# USB_Downstream_Type_C_Port_3.net
KiCad netlist of a schematic drawn in Altium Designer
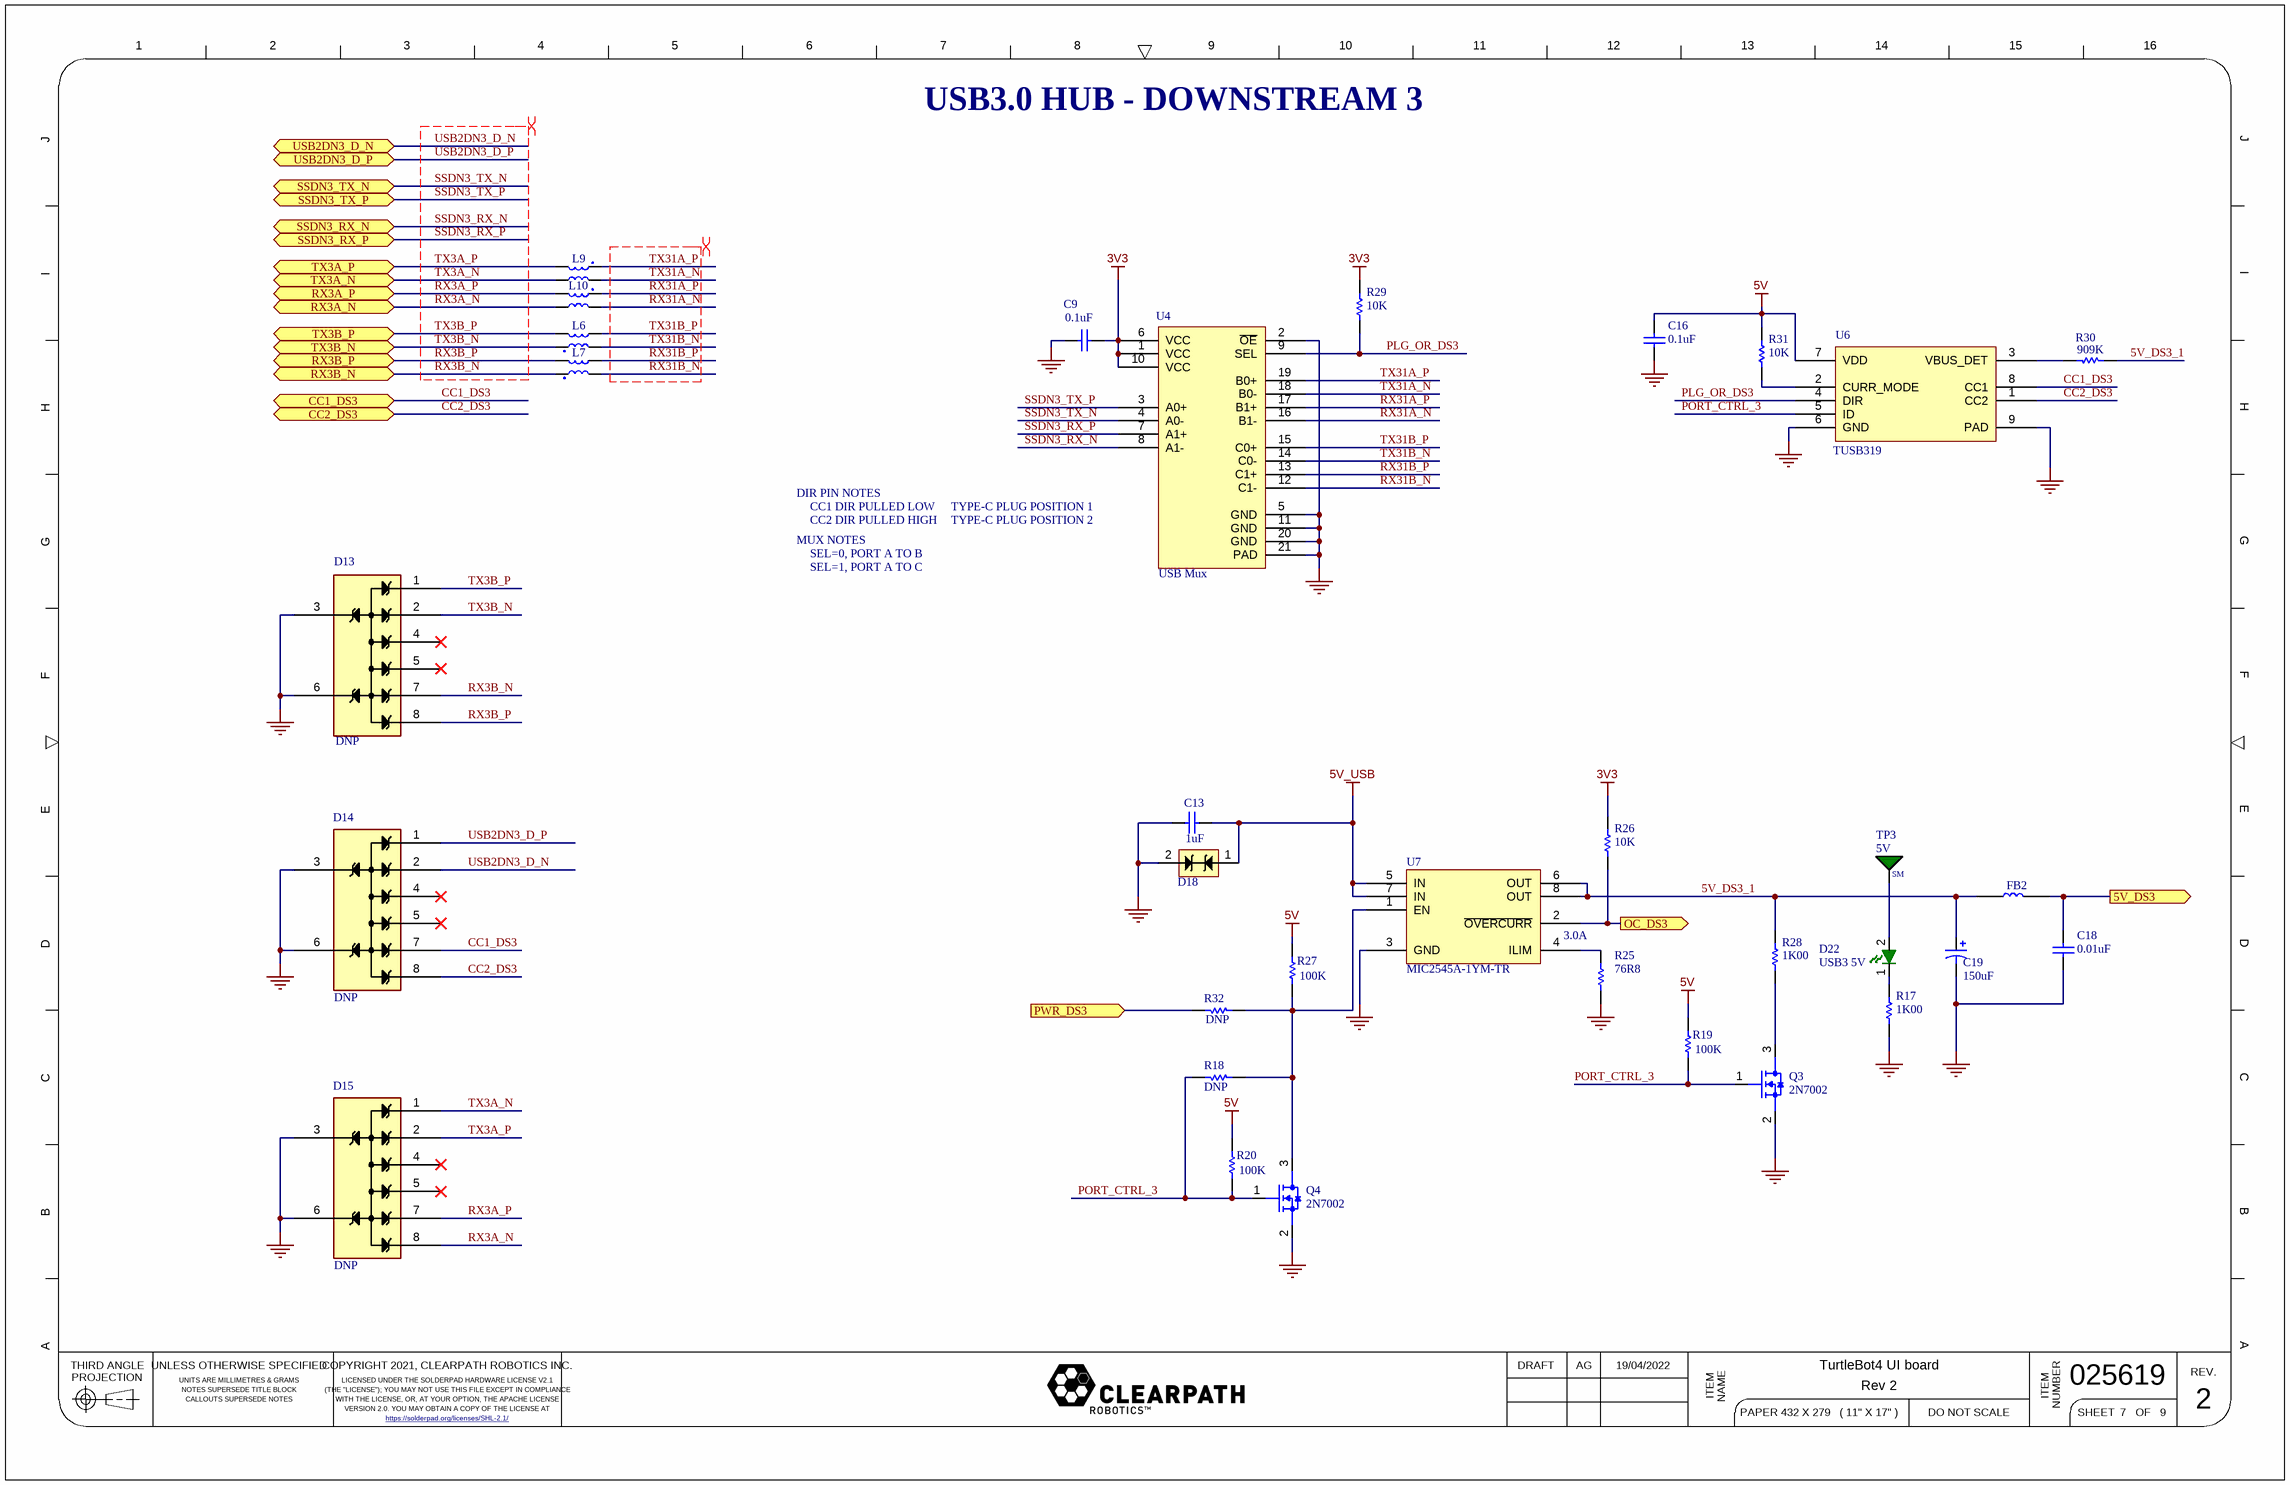
[diagram p0: USB Downstream Type C Port 3.SchDoc]

(export (version "E")
  (design (tool "Eeschema 10.0.6"))
  (components
    (comp (ref "C9")
      (value "0.1uF")
      (footprint "C0805")
      (description "Capacitor")
      (fields (field (name "TOLERANCE") "10%") (field (name "VOLTAGE") "50V"))
      (libsource (lib "CPR_CommonDevices") (part "Capacitor _SMT"))
    )
    (comp (ref "C13")
      (value "1uF")
      (footprint "C0805")
      (description "Capacitor")
      (fields (field (name "TOLERANCE") "-20 +80") (field (name "VOLTAGE") "50V"))
      (libsource (lib "CPR_CommonDevices") (part "Capacitor _SMT"))
    )
    (comp (ref "C16")
      (value "0.1uF")
      (footprint "C0805")
      (description "Capacitor")
      (fields (field (name "TOLERANCE") "10%") (field (name "VOLTAGE") "50V"))
      (libsource (lib "CPR_CommonDevices") (part "Capacitor _SMT"))
    )
    (comp (ref "C18")
      (value "0.01uF")
      (footprint "C0805")
      (description "Capacitor")
      (fields (field (name "TOLERANCE") "10%") (field (name "VOLTAGE") "50V"))
      (libsource (lib "CPR_CommonDevices") (part "Capacitor _SMT"))
    )
    (comp (ref "C19")
      (value "150uF")
      (footprint "T494D157K016AT:CAPMP7.6X4.3_3.1N_KEM-M")
      (description "CAP TANT 150UF 10% 16V 2917")
      (fields (field (name "VOLTAGE") "16V") (field (name "TOLERANCE") "10%"))
      (libsource (lib "Miscellaneous Devices") (part "Cap Pol1"))
    )
    (comp (ref "D13")
      (value "DNP")
      (footprint "ESD7016")
      (description "USB3 TVS diode assy")
      (fields (field (name "MFG") "ON Semi"))
      (libsource (lib "ONSemi_ESD7016") (part "ESD7016"))
    )
    (comp (ref "D14")
      (value "DNP")
      (footprint "ESD7016")
      (description "USB3 TVS diode assy")
      (fields (field (name "MFG") "ON Semi"))
      (libsource (lib "ONSemi_ESD7016") (part "ESD7016"))
    )
    (comp (ref "D15")
      (value "DNP")
      (footprint "ESD7016")
      (description "USB3 TVS diode assy")
      (fields (field (name "MFG") "ON Semi"))
      (libsource (lib "ONSemi_ESD7016") (part "ESD7016"))
    )
    (comp (ref "D18")
      (value "TVS DIODE BIDIR 15V SMC")
      (footprint "General PCB Library:DO-214AA")
      (description "TVS 600W 15V BI-DIR DO-214AA")
      (fields (field (name "MFG") "Littelfuse Inc."))
      (libsource (lib "SMBJ15CA") (part "TVS DIODE BIDIR 15V SMC"))
    )
    (comp (ref "D22")
      (value "USB3 5V")
      (footprint "LED_0805_GRN")
      (description "Green LED")
      (fields (field (name "MFG") "LiteOn"))
      (libsource (lib "Green LED") (part "GREEN_LED"))
    )
    (comp (ref "FB2")
      (value "742792602")
      (footprint "General PCB Library:R0603")
      (description "60 Ohms 1 Signal Line Ferrite Bead 0603 (1608 Metric) 3A 40mOhm")
      (libsource (lib "742792602") (part "742792602"))
    )
    (comp (ref "L6")
      (value "CMC 100MA 2LN 90 OHM SMD2")
      (footprint "cmc_90_ohms:cmc_90_ohms")
      (description "Line Common Mode Choke Surface Mount 90 Ohms 100mA DCR 5Ohm")
      (libsource (lib "cmc_90_ohms") (part "CMC 90_Ohms"))
    )
    (comp (ref "L7")
      (value "CMC 100MA 2LN 90 OHM SMD2")
      (footprint "cmc_90_ohms:cmc_90_ohms")
      (description "Line Common Mode Choke Surface Mount 90 Ohms 100mA DCR 5Ohm")
      (libsource (lib "cmc_90_ohms") (part "CMC 90_Ohms"))
    )
    (comp (ref "L9")
      (value "CMC 100MA 2LN 90 OHM SMD2")
      (footprint "cmc_90_ohms:cmc_90_ohms")
      (description "Line Common Mode Choke Surface Mount 90 Ohms 100mA DCR 5Ohm")
      (libsource (lib "cmc_90_ohms") (part "CMC 90_Ohms"))
    )
    (comp (ref "L10")
      (value "CMC 100MA 2LN 90 OHM SMD2")
      (footprint "cmc_90_ohms:cmc_90_ohms")
      (description "Line Common Mode Choke Surface Mount 90 Ohms 100mA DCR 5Ohm")
      (libsource (lib "cmc_90_ohms") (part "CMC 90_Ohms"))
    )
    (comp (ref "Q3")
      (value "NFET")
      (footprint "SOT-23-3")
      (fields (field (name "MFG PN") "2N7002") (field (name "MFG") "ON Semi"))
      (libsource (lib "NFET_SINGLE") (part "NFET_SNGL"))
    )
    (comp (ref "Q4")
      (value "NFET")
      (footprint "SOT-23-3")
      (fields (field (name "MFG PN") "2N7002") (field (name "MFG") "ON Semi"))
      (libsource (lib "NFET_SINGLE") (part "NFET_SNGL"))
    )
    (comp (ref "R17")
      (value "1K00")
      (footprint "R0805")
      (description "Resistor")
      (fields (field (name "TOLERANCE") "1%") (field (name "MFG") "Yageo"))
      (libsource (lib "CPR_CommonDevices") (part "Resistor_SMT"))
    )
    (comp (ref "R18")
      (value "DNP")
      (footprint "R0805")
      (description "Resistor")
      (fields (field (name "MFG") "Yageo") (field (name "Comment") "Resistor_SMT"))
      (libsource (lib "") (part "Resistor_SMT_1"))
    )
    (comp (ref "R19")
      (value "100K")
      (footprint "R0805")
      (description "Resistor")
      (fields (field (name "TOLERANCE") "1%") (field (name "MFG") "Yageo"))
      (libsource (lib "CPR_CommonDevices") (part "Resistor_SMT"))
    )
    (comp (ref "R20")
      (value "100K")
      (footprint "R0805")
      (description "Resistor")
      (fields (field (name "TOLERANCE") "1%") (field (name "MFG") "Yageo"))
      (libsource (lib "CPR_CommonDevices") (part "Resistor_SMT"))
    )
    (comp (ref "R25")
      (value "3.0A")
      (footprint "R0805")
      (description "Resistor")
      (fields
        (field (name "ALTIUM_VALUE") "76R8")
        (field (name "TOLERANCE") "1%")
        (field (name "MFG") "Yageo")
      )
      (libsource (lib "CPR_CommonDevices") (part "Resistor_SMT"))
    )
    (comp (ref "R26")
      (value "10K")
      (footprint "R0805")
      (description "Resistor")
      (fields (field (name "TOLERANCE") "1%") (field (name "MFG") "Yageo"))
      (libsource (lib "CPR_CommonDevices") (part "Resistor_SMT"))
    )
    (comp (ref "R27")
      (value "100K")
      (footprint "R0805")
      (description "Resistor")
      (fields (field (name "TOLERANCE") "1%") (field (name "MFG") "Yageo"))
      (libsource (lib "CPR_CommonDevices") (part "Resistor_SMT"))
    )
    (comp (ref "R28")
      (value "1K00")
      (footprint "R0805")
      (description "Resistor")
      (fields (field (name "TOLERANCE") "1%") (field (name "MFG") "Yageo"))
      (libsource (lib "CPR_CommonDevices") (part "Resistor_SMT"))
    )
    (comp (ref "R29")
      (value "10K")
      (footprint "R0805")
      (description "Resistor")
      (fields (field (name "TOLERANCE") "1%") (field (name "MFG") "Yageo"))
      (libsource (lib "CPR_CommonDevices") (part "Resistor_SMT"))
    )
    (comp (ref "R30")
      (value "909K")
      (footprint "R0805")
      (description "Resistor")
      (fields (field (name "TOLERANCE") "1%") (field (name "MFG") "Yageo"))
      (libsource (lib "CPR_CommonDevices") (part "Resistor_SMT"))
    )
    (comp (ref "R31")
      (value "10K")
      (footprint "R0805")
      (description "Resistor")
      (fields (field (name "TOLERANCE") "1%") (field (name "MFG") "Yageo"))
      (libsource (lib "CPR_CommonDevices") (part "Resistor_SMT"))
    )
    (comp (ref "R32")
      (value "DNP")
      (footprint "R0805")
      (description "Resistor")
      (fields (field (name "MFG") "Yageo") (field (name "Comment") "Resistor_SMT"))
      (libsource (lib "") (part "Resistor_SMT_1"))
    )
    (comp (ref "TP3")
      (value "5V")
      (footprint "TP_28SM")
      (description "Test point, 28 Mil exposed pad")
      (fields (field (name "MANUFACTURER") "Clearpath Robotics Inc."))
      (libsource (lib "Test Points") (part "TP_28SM"))
    )
    (comp (ref "U4")
      (value "USB Mux")
      (footprint "TQFN20")
      (description "TC7PCI3212MT,LF USB3.0 Mux")
      (fields (field (name "MANUFACTURER") "Toshiba"))
      (libsource (lib "TOSHIBA TC7PCI3212MT") (part "TC7PCI3212"))
    )
    (comp (ref "U6")
      (value "TUSB319")
      (footprint "WSON8")
      (description "USB Type C Controller")
      (fields (field (name "MFG") "Texas Instruments"))
      (libsource (lib "TUSB319") (part "TUSB319"))
    )
    (comp (ref "U7")
      (value "MIC2545_USB_SWITCH")
      (footprint "General PCB Library:SOIC-8-150")
      (description "IC PWR SWITCH N-CHAN 1:1 8SOIC")
      (fields (field (name "MFG PN") "MIC2545A-1YM-TR") (field (name "MANUFACTURER") "Microchip"))
      (libsource (lib "MIC2545") (part "MIC2545_USB_SWITCH"))
    )
  )
  (nets
    (net (code "1") (name "/5V_DS3") (class "Default")
      (node (ref "C18") (pin "1") (pinfunction "1_1") (pintype "passive"))
      (node (ref "FB2") (pin "2") (pinfunction "2_2") (pintype "passive"))
    )
    (net (code "2") (name "/5V_DS3_1") (class "Default")
      (node (ref "C19") (pin "1") (pinfunction "1_1") (pintype "passive"))
      (node (ref "FB2") (pin "1") (pinfunction "1_1") (pintype "passive"))
      (node (ref "R28") (pin "1") (pinfunction "1_1") (pintype "passive"))
      (node (ref "R30") (pin "2") (pinfunction "2_2") (pintype "passive"))
      (node (ref "U7") (pin "6") (pinfunction "OUT_6") (pintype "passive"))
      (node (ref "U7") (pin "8") (pinfunction "OUT_8") (pintype "passive"))
    )
    (net (code "3") (name "/CC1_DS3") (class "Default")
      (node (ref "D14") (pin "7") (pintype "passive"))
      (node (ref "U6") (pin "8") (pinfunction "CC1_8") (pintype "passive"))
    )
    (net (code "4") (name "/CC2_DS3") (class "Default")
      (node (ref "D14") (pin "8") (pintype "passive"))
      (node (ref "U6") (pin "1") (pinfunction "CC2_1") (pintype "passive"))
    )
    (net (code "5") (name "/OC_DS3") (class "Default")
      (node (ref "R26") (pin "2") (pinfunction "2_2") (pintype "passive"))
      (node (ref "U7") (pin "2") (pinfunction "~{OVERCURR}_2") (pintype "passive"))
    )
    (net (code "6") (name "/PLG_OR_DS3") (class "Default")
      (node (ref "R29") (pin "2") (pinfunction "2_2") (pintype "passive"))
      (node (ref "U4") (pin "9") (pinfunction "SEL_9") (pintype "passive"))
      (node (ref "U6") (pin "4") (pinfunction "DIR_4") (pintype "passive"))
    )
    (net (code "7") (name "/PORT_CTRL_3") (class "Default")
      (node (ref "Q3") (pin "1") (pinfunction "G1_1") (pintype "passive"))
      (node (ref "Q4") (pin "1") (pinfunction "G1_1") (pintype "passive"))
      (node (ref "R18") (pin "1") (pinfunction "1_1") (pintype "passive"))
      (node (ref "R19") (pin "1") (pinfunction "1_1") (pintype "passive"))
      (node (ref "R20") (pin "1") (pinfunction "1_1") (pintype "passive"))
      (node (ref "U6") (pin "5") (pinfunction "ID_5") (pintype "passive"))
    )
    (net (code "8") (name "/PWR_DS3") (class "Default")
      (node (ref "R32") (pin "1") (pinfunction "1_1") (pintype "passive"))
    )
    (net (code "9") (name "/RX3A_N") (class "Default")
      (node (ref "D15") (pin "8") (pintype "passive"))
      (node (ref "L10") (pin "3") (pinfunction "3_3") (pintype "passive"))
    )
    (net (code "10") (name "/RX3A_P") (class "Default")
      (node (ref "D15") (pin "7") (pintype "passive"))
      (node (ref "L10") (pin "4") (pinfunction "4_4") (pintype "passive"))
    )
    (net (code "11") (name "/RX3B_N") (class "Default")
      (node (ref "D13") (pin "7") (pintype "passive"))
      (node (ref "L7") (pin "1") (pinfunction "1_1") (pintype "passive"))
    )
    (net (code "12") (name "/RX3B_P") (class "Default")
      (node (ref "D13") (pin "8") (pintype "passive"))
      (node (ref "L7") (pin "2") (pinfunction "2_2") (pintype "passive"))
    )
    (net (code "13") (name "/RX31A_N") (class "Default")
      (node (ref "L10") (pin "2") (pinfunction "2_2") (pintype "passive"))
      (node (ref "U4") (pin "16") (pinfunction "B1-_16") (pintype "passive"))
    )
    (net (code "14") (name "/RX31A_P") (class "Default")
      (node (ref "L10") (pin "1") (pinfunction "1_1") (pintype "passive"))
      (node (ref "U4") (pin "17") (pinfunction "B1+_17") (pintype "passive"))
    )
    (net (code "15") (name "/RX31B_N") (class "Default")
      (node (ref "L7") (pin "4") (pinfunction "4_4") (pintype "passive"))
      (node (ref "U4") (pin "12") (pinfunction "C1-_12") (pintype "passive"))
    )
    (net (code "16") (name "/RX31B_P") (class "Default")
      (node (ref "L7") (pin "3") (pinfunction "3_3") (pintype "passive"))
      (node (ref "U4") (pin "13") (pinfunction "C1+_13") (pintype "passive"))
    )
    (net (code "17") (name "/SSDN3_RX_N") (class "Default")
      (node (ref "U4") (pin "8") (pinfunction "A1-_8") (pintype "passive"))
    )
    (net (code "18") (name "/SSDN3_RX_P") (class "Default")
      (node (ref "U4") (pin "7") (pinfunction "A1+_7") (pintype "passive"))
    )
    (net (code "19") (name "/SSDN3_TX_N") (class "Default")
      (node (ref "U4") (pin "4") (pinfunction "A0-_4") (pintype "passive"))
    )
    (net (code "20") (name "/SSDN3_TX_P") (class "Default")
      (node (ref "U4") (pin "3") (pinfunction "A0+_3") (pintype "passive"))
    )
    (net (code "21") (name "/TX3A_N") (class "Default")
      (node (ref "D15") (pin "1") (pinfunction "1_1") (pintype "passive"))
      (node (ref "L9") (pin "3") (pinfunction "3_3") (pintype "passive"))
    )
    (net (code "22") (name "/TX3A_P") (class "Default")
      (node (ref "D15") (pin "2") (pintype "passive"))
      (node (ref "L9") (pin "4") (pinfunction "4_4") (pintype "passive"))
    )
    (net (code "23") (name "/TX3B_N") (class "Default")
      (node (ref "D13") (pin "2") (pintype "passive"))
      (node (ref "L6") (pin "1") (pinfunction "1_1") (pintype "passive"))
    )
    (net (code "24") (name "/TX3B_P") (class "Default")
      (node (ref "D13") (pin "1") (pinfunction "1_1") (pintype "passive"))
      (node (ref "L6") (pin "2") (pinfunction "2_2") (pintype "passive"))
    )
    (net (code "25") (name "/TX31A_N") (class "Default")
      (node (ref "L9") (pin "2") (pinfunction "2_2") (pintype "passive"))
      (node (ref "U4") (pin "18") (pinfunction "B0-_18") (pintype "passive"))
    )
    (net (code "26") (name "/TX31A_P") (class "Default")
      (node (ref "L9") (pin "1") (pinfunction "1_1") (pintype "passive"))
      (node (ref "U4") (pin "19") (pinfunction "B0+_19") (pintype "passive"))
    )
    (net (code "27") (name "/TX31B_N") (class "Default")
      (node (ref "L6") (pin "4") (pinfunction "4_4") (pintype "passive"))
      (node (ref "U4") (pin "14") (pinfunction "C0-_14") (pintype "passive"))
    )
    (net (code "28") (name "/TX31B_P") (class "Default")
      (node (ref "L6") (pin "3") (pinfunction "3_3") (pintype "passive"))
      (node (ref "U4") (pin "15") (pinfunction "C0+_15") (pintype "passive"))
    )
    (net (code "29") (name "/USB2DN3_D_N") (class "Default") (node (ref "D14") (pin "2") (pintype "passive")))
    (net (code "30") (name "/USB2DN3_D_P") (class "Default")
      (node (ref "D14") (pin "1") (pinfunction "1_1") (pintype "passive"))
    )
    (net (code "31") (name "3V3") (class "Default")
      (node (ref "C9") (pin "1") (pinfunction "1_1") (pintype "passive"))
      (node (ref "R26") (pin "1") (pinfunction "1_1") (pintype "passive"))
      (node (ref "R29") (pin "1") (pinfunction "1_1") (pintype "passive"))
      (node (ref "U4") (pin "1") (pinfunction "VCC_1") (pintype "passive"))
      (node (ref "U4") (pin "10") (pinfunction "VCC_10") (pintype "passive"))
      (node (ref "U4") (pin "6") (pinfunction "VCC_6") (pintype "passive"))
    )
    (net (code "32") (name "5V") (class "Default")
      (node (ref "C16") (pin "1") (pinfunction "1_1") (pintype "passive"))
      (node (ref "R19") (pin "2") (pinfunction "2_2") (pintype "passive"))
      (node (ref "R20") (pin "2") (pinfunction "2_2") (pintype "passive"))
      (node (ref "R27") (pin "2") (pinfunction "2_2") (pintype "passive"))
      (node (ref "R31") (pin "1") (pinfunction "1_1") (pintype "passive"))
      (node (ref "U6") (pin "7") (pinfunction "VDD_7") (pintype "passive"))
    )
    (net (code "33") (name "5V_USB") (class "Default")
      (node (ref "C13") (pin "2") (pinfunction "2_2") (pintype "passive"))
      (node (ref "D18") (pin "1") (pintype "passive"))
      (node (ref "U7") (pin "5") (pinfunction "IN_5") (pintype "passive"))
      (node (ref "U7") (pin "7") (pinfunction "IN_7") (pintype "passive"))
    )
    (net (code "34") (name "GND") (class "Default")
      (node (ref "C13") (pin "1") (pinfunction "1_1") (pintype "passive"))
      (node (ref "C16") (pin "2") (pinfunction "2_2") (pintype "passive"))
      (node (ref "C18") (pin "2") (pinfunction "2_2") (pintype "passive"))
      (node (ref "C19") (pin "2") (pinfunction "2_2") (pintype "passive"))
      (node (ref "C9") (pin "2") (pinfunction "2_2") (pintype "passive"))
      (node (ref "D13") (pin "3") (pintype "passive"))
      (node (ref "D13") (pin "6") (pintype "passive"))
      (node (ref "D14") (pin "3") (pintype "passive"))
      (node (ref "D14") (pin "6") (pintype "passive"))
      (node (ref "D15") (pin "3") (pintype "passive"))
      (node (ref "D15") (pin "6") (pintype "passive"))
      (node (ref "D18") (pin "2") (pintype "passive"))
      (node (ref "Q3") (pin "2") (pinfunction "D1_2") (pintype "passive"))
      (node (ref "Q4") (pin "2") (pinfunction "D1_2") (pintype "passive"))
      (node (ref "R17") (pin "2") (pinfunction "2_2") (pintype "passive"))
      (node (ref "R25") (pin "1") (pinfunction "1_1") (pintype "passive"))
      (node (ref "U4") (pin "11") (pinfunction "GND_11") (pintype "passive"))
      (node (ref "U4") (pin "2") (pinfunction "~{OE}_2") (pintype "passive"))
      (node (ref "U4") (pin "20") (pinfunction "GND_20") (pintype "passive"))
      (node (ref "U4") (pin "21") (pinfunction "PAD_21") (pintype "passive"))
      (node (ref "U4") (pin "5") (pinfunction "GND_5") (pintype "passive"))
      (node (ref "U6") (pin "6") (pinfunction "GND_6") (pintype "passive"))
      (node (ref "U6") (pin "9") (pinfunction "PAD_9") (pintype "passive"))
      (node (ref "U7") (pin "3") (pinfunction "GND_3") (pintype "passive"))
    )
    (net (code "35") (name "Net-(D22-RA)") (class "Default")
      (node (ref "D22") (pin "2") (pinfunction "RA_2") (pintype "passive"))
      (node (ref "TP3") (pin "1") (pintype "passive"))
    )
    (net (code "36") (name "Net-(D22-RK)") (class "Default")
      (node (ref "D22") (pin "1") (pinfunction "RK_1") (pintype "passive"))
      (node (ref "R17") (pin "1") (pinfunction "1_1") (pintype "passive"))
    )
    (net (code "37") (name "Net-(Q3-S1)") (class "Default")
      (node (ref "Q3") (pin "3") (pinfunction "S1_3") (pintype "passive"))
      (node (ref "R28") (pin "2") (pinfunction "2_2") (pintype "passive"))
    )
    (net (code "38") (name "Net-(Q4-S1)") (class "Default")
      (node (ref "Q4") (pin "3") (pinfunction "S1_3") (pintype "passive"))
      (node (ref "R18") (pin "2") (pinfunction "2_2") (pintype "passive"))
      (node (ref "R27") (pin "1") (pinfunction "1_1") (pintype "passive"))
      (node (ref "R32") (pin "2") (pinfunction "2_2") (pintype "passive"))
      (node (ref "U7") (pin "1") (pinfunction "EN_1") (pintype "passive"))
    )
    (net (code "39") (name "Net-(U6-CURR_MODE)") (class "Default")
      (node (ref "R31") (pin "2") (pinfunction "2_2") (pintype "passive"))
      (node (ref "U6") (pin "2") (pinfunction "CURR_MODE_2") (pintype "passive"))
    )
    (net (code "40") (name "Net-(U6-VBUS_DET)") (class "Default")
      (node (ref "R30") (pin "1") (pinfunction "1_1") (pintype "passive"))
      (node (ref "U6") (pin "3") (pinfunction "VBUS_DET_3") (pintype "passive"))
    )
    (net (code "41") (name "Net-(U7-ILIM)") (class "Default")
      (node (ref "R25") (pin "2") (pinfunction "2_2") (pintype "passive"))
      (node (ref "U7") (pin "4") (pinfunction "ILIM_4") (pintype "passive"))
    )
    (net (code "42") (name "unconnected-(D13-Pad4)") (class "Default")
      (node (ref "D13") (pin "4") (pintype "passive+no_connect"))
    )
    (net (code "43") (name "unconnected-(D13-Pad5)") (class "Default")
      (node (ref "D13") (pin "5") (pintype "passive+no_connect"))
    )
    (net (code "44") (name "unconnected-(D14-Pad4)") (class "Default")
      (node (ref "D14") (pin "4") (pintype "passive+no_connect"))
    )
    (net (code "45") (name "unconnected-(D14-Pad5)") (class "Default")
      (node (ref "D14") (pin "5") (pintype "passive+no_connect"))
    )
    (net (code "46") (name "unconnected-(D15-Pad4)") (class "Default")
      (node (ref "D15") (pin "4") (pintype "passive+no_connect"))
    )
    (net (code "47") (name "unconnected-(D15-Pad5)") (class "Default")
      (node (ref "D15") (pin "5") (pintype "passive+no_connect"))
    )
  )
)
